# LAUNCHXL-F28379D_3.net
KiCad netlist of a schematic drawn in Altium Designer
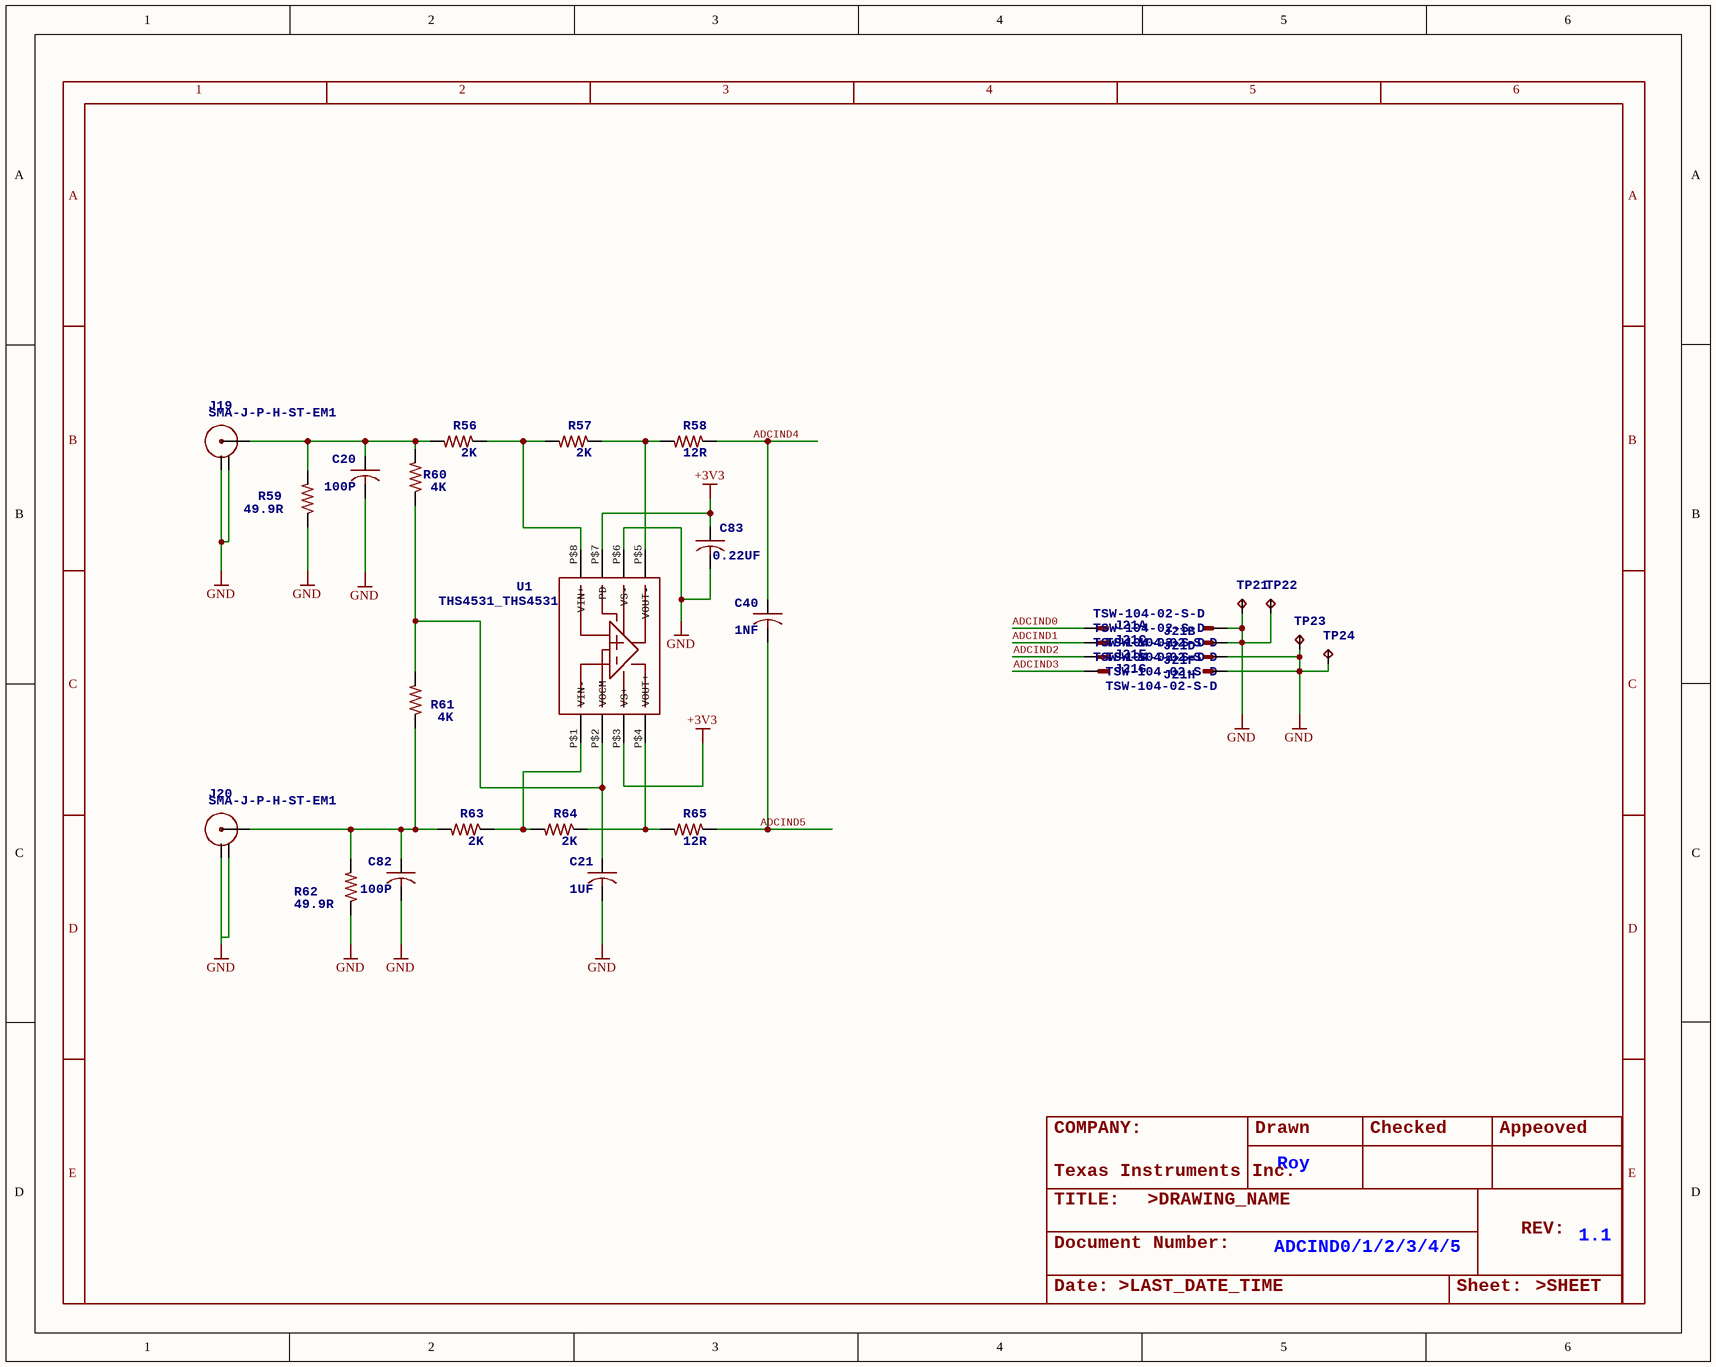
[diagram p0: LAUNCHXL-F28379D_3.SchDoc]

(export (version "E")
  (design (tool "Eeschema 10.0.6"))
  (components
    (comp (ref "C20")
      (value "100P")
      (footprint "C0402")
      (description "<B>CAPACITOR</B>, American symbol")
      (libsource (lib "rcl") (part "C-USC0402"))
    )
    (comp (ref "C21")
      (value "1UF")
      (footprint "C0402")
      (description "<B>CAPACITOR</B>, American symbol")
      (libsource (lib "rcl") (part "C-USC0402"))
    )
    (comp (ref "C40")
      (value "1NF")
      (footprint "C0402")
      (description "<B>CAPACITOR</B>, American symbol")
      (libsource (lib "rcl") (part "C-USC0402"))
    )
    (comp (ref "C82")
      (value "100P")
      (footprint "C0402")
      (description "<B>CAPACITOR</B>, American symbol")
      (libsource (lib "rcl") (part "C-USC0402"))
    )
    (comp (ref "C83")
      (value "0.22UF")
      (footprint "C0402")
      (description "<B>CAPACITOR</B>, American symbol")
      (libsource (lib "rcl") (part "C-USC0402"))
    )
    (comp (ref "J19") (value "SMA-J-P-H-ST-EM1") (footprint "SMA_EM") (libsource (lib "ads704") (part "SMA")))
    (comp (ref "J20") (value "SMA-J-P-H-ST-EM1") (footprint "SMA_EM") (libsource (lib "ads704") (part "SMA")))
    (comp (ref "J21")
      (value "TSW-104-02-S-D")
      (footprint "TSW-104-02-S-D")
      (description "<b>THROUGH-HOLE .025\" SQ POST HEADER</b><p>\nSource: Samtec TSW.pdf")
      (libsource (lib "") (part "TSW-104-02-S-D_1"))
    )
    (comp (ref "R56")
      (value "2K")
      (footprint "R0402")
      (description "<B>RESISTOR</B>, American symbol")
      (libsource (lib "rcl") (part "R-US_R0402"))
    )
    (comp (ref "R57")
      (value "2K")
      (footprint "R0402")
      (description "<B>RESISTOR</B>, American symbol")
      (libsource (lib "rcl") (part "R-US_R0402"))
    )
    (comp (ref "R58")
      (value "12R")
      (footprint "R0402")
      (description "<B>RESISTOR</B>, American symbol")
      (libsource (lib "rcl") (part "R-US_R0402"))
    )
    (comp (ref "R59")
      (value "49.9R")
      (footprint "R0402")
      (description "<B>RESISTOR</B>, American symbol")
      (libsource (lib "rcl") (part "R-US_R0402"))
    )
    (comp (ref "R60")
      (value "4K")
      (footprint "R0402")
      (description "<B>RESISTOR</B>, American symbol")
      (libsource (lib "rcl") (part "R-US_R0402"))
    )
    (comp (ref "R61")
      (value "4K")
      (footprint "R0402")
      (description "<B>RESISTOR</B>, American symbol")
      (libsource (lib "rcl") (part "R-US_R0402"))
    )
    (comp (ref "R62")
      (value "49.9R")
      (footprint "R0402")
      (description "<B>RESISTOR</B>, American symbol")
      (libsource (lib "rcl") (part "R-US_R0402"))
    )
    (comp (ref "R63")
      (value "2K")
      (footprint "R0402")
      (description "<B>RESISTOR</B>, American symbol")
      (libsource (lib "rcl") (part "R-US_R0402"))
    )
    (comp (ref "R64")
      (value "2K")
      (footprint "R0402")
      (description "<B>RESISTOR</B>, American symbol")
      (libsource (lib "rcl") (part "R-US_R0402"))
    )
    (comp (ref "R65")
      (value "12R")
      (footprint "R0402")
      (description "<B>RESISTOR</B>, American symbol")
      (libsource (lib "rcl") (part "R-US_R0402"))
    )
    (comp (ref "TP21")
      (value "TESTPAD_TPB1,27")
      (footprint "TESTPAD_B1,27")
      (description "<b>Test pad</b>")
      (libsource (lib "RF430FRL152H_EVM_a") (part "TESTPAD_TPB1,27"))
    )
    (comp (ref "TP22")
      (value "TESTPAD_TPB1,27")
      (footprint "TESTPAD_B1,27")
      (description "<b>Test pad</b>")
      (libsource (lib "RF430FRL152H_EVM_a") (part "TESTPAD_TPB1,27"))
    )
    (comp (ref "TP23")
      (value "TESTPAD_TPB1,27")
      (footprint "TESTPAD_B1,27")
      (description "<b>Test pad</b>")
      (libsource (lib "RF430FRL152H_EVM_a") (part "TESTPAD_TPB1,27"))
    )
    (comp (ref "TP24")
      (value "TESTPAD_TPB1,27")
      (footprint "TESTPAD_B1,27")
      (description "<b>Test pad</b>")
      (libsource (lib "RF430FRL152H_EVM_a") (part "TESTPAD_TPB1,27"))
    )
    (comp (ref "U1")
      (value "THS4531_THS4531")
      (footprint "THS4531_THS4531")
      (libsource (lib "THS4531") (part "THS4531_THS4531"))
    )
  )
  (nets
    (net (code "1") (name "+3V3") (class "Default")
      (node (ref "C83") (pin "1") (pinfunction "1_1") (pintype "passive"))
      (node (ref "U1") (pin "P$3") (pinfunction "VS+_P$3") (pintype "passive"))
      (node (ref "U1") (pin "P$7") (pinfunction "PD_P$7") (pintype "passive"))
    )
    (net (code "2") (name "/ADCIND0") (class "Default")
      (node (ref "J21") (pin "1") (pinfunction "1_1") (pintype "passive"))
    )
    (net (code "3") (name "/ADCIND1") (class "Default")
      (node (ref "J21") (pin "3") (pinfunction "1_3") (pintype "passive"))
    )
    (net (code "4") (name "/ADCIND2") (class "Default")
      (node (ref "J21") (pin "5") (pinfunction "1_5") (pintype "passive"))
    )
    (net (code "5") (name "/ADCIND3") (class "Default")
      (node (ref "J21") (pin "7") (pinfunction "1_7") (pintype "passive"))
    )
    (net (code "6") (name "/ADCIND4") (class "Default")
      (node (ref "C40") (pin "1") (pinfunction "1_1") (pintype "passive"))
      (node (ref "R58") (pin "1") (pinfunction "1_1") (pintype "passive"))
    )
    (net (code "7") (name "/ADCIND5") (class "Default")
      (node (ref "C40") (pin "2") (pinfunction "2_2") (pintype "passive"))
      (node (ref "R65") (pin "1") (pinfunction "1_1") (pintype "passive"))
    )
    (net (code "8") (name "GND") (class "Default")
      (node (ref "C20") (pin "2") (pinfunction "2_2") (pintype "passive"))
      (node (ref "C21") (pin "2") (pinfunction "2_2") (pintype "passive"))
      (node (ref "C82") (pin "2") (pinfunction "2_2") (pintype "passive"))
      (node (ref "C83") (pin "2") (pinfunction "2_2") (pintype "passive"))
      (node (ref "J19") (pin "1") (pinfunction "1_1") (pintype "passive"))
      (node (ref "J19") (pin "3_4_5") (pinfunction "3_3_4_5") (pintype "passive"))
      (node (ref "J20") (pin "1") (pinfunction "1_1") (pintype "passive"))
      (node (ref "J20") (pin "3_4_5") (pinfunction "3_3_4_5") (pintype "passive"))
      (node (ref "J21") (pin "2") (pinfunction "1_2") (pintype "passive"))
      (node (ref "J21") (pin "4") (pinfunction "1_4") (pintype "passive"))
      (node (ref "J21") (pin "6") (pinfunction "1_6") (pintype "passive"))
      (node (ref "J21") (pin "8") (pinfunction "1_8") (pintype "passive"))
      (node (ref "R59") (pin "1") (pinfunction "1_1") (pintype "passive"))
      (node (ref "R62") (pin "1") (pinfunction "1_1") (pintype "passive"))
      (node (ref "TP21") (pin "TP") (pinfunction "TP_TP") (pintype "passive"))
      (node (ref "TP22") (pin "TP") (pinfunction "TP_TP") (pintype "passive"))
      (node (ref "TP23") (pin "TP") (pinfunction "TP_TP") (pintype "passive"))
      (node (ref "TP24") (pin "TP") (pinfunction "TP_TP") (pintype "passive"))
      (node (ref "U1") (pin "P$6") (pinfunction "VS-_P$6") (pintype "passive"))
    )
    (net (code "9") (name "Net-(C20-Pad1)") (class "Default")
      (node (ref "C20") (pin "1") (pinfunction "1_1") (pintype "passive"))
      (node (ref "J19") (pin "2") (pinfunction "2_2") (pintype "passive"))
      (node (ref "R56") (pin "2") (pinfunction "2_2") (pintype "passive"))
      (node (ref "R59") (pin "2") (pinfunction "2_2") (pintype "passive"))
      (node (ref "R60") (pin "2") (pinfunction "2_2") (pintype "passive"))
    )
    (net (code "10") (name "Net-(C82-Pad1)") (class "Default")
      (node (ref "C82") (pin "1") (pinfunction "1_1") (pintype "passive"))
      (node (ref "J20") (pin "2") (pinfunction "2_2") (pintype "passive"))
      (node (ref "R61") (pin "1") (pinfunction "1_1") (pintype "passive"))
      (node (ref "R62") (pin "2") (pinfunction "2_2") (pintype "passive"))
      (node (ref "R63") (pin "2") (pinfunction "2_2") (pintype "passive"))
    )
    (net (code "11") (name "Net-(U1-VIN+)") (class "Default")
      (node (ref "R56") (pin "1") (pinfunction "1_1") (pintype "passive"))
      (node (ref "R57") (pin "2") (pinfunction "2_2") (pintype "passive"))
      (node (ref "U1") (pin "P$8") (pinfunction "VIN+_P$8") (pintype "passive"))
    )
    (net (code "12") (name "Net-(U1-VIN-)") (class "Default")
      (node (ref "R63") (pin "1") (pinfunction "1_1") (pintype "passive"))
      (node (ref "R64") (pin "2") (pinfunction "2_2") (pintype "passive"))
      (node (ref "U1") (pin "P$1") (pinfunction "VIN-_P$1") (pintype "passive"))
    )
    (net (code "13") (name "Net-(U1-VOCM)") (class "Default")
      (node (ref "C21") (pin "1") (pinfunction "1_1") (pintype "passive"))
      (node (ref "R60") (pin "1") (pinfunction "1_1") (pintype "passive"))
      (node (ref "R61") (pin "2") (pinfunction "2_2") (pintype "passive"))
      (node (ref "U1") (pin "P$2") (pinfunction "VOCM_P$2") (pintype "passive"))
    )
    (net (code "14") (name "Net-(U1-VOUT+)") (class "Default")
      (node (ref "R64") (pin "1") (pinfunction "1_1") (pintype "passive"))
      (node (ref "R65") (pin "2") (pinfunction "2_2") (pintype "passive"))
      (node (ref "U1") (pin "P$4") (pinfunction "VOUT+_P$4") (pintype "passive"))
    )
    (net (code "15") (name "Net-(U1-VOUT-)") (class "Default")
      (node (ref "R57") (pin "1") (pinfunction "1_1") (pintype "passive"))
      (node (ref "R58") (pin "2") (pinfunction "2_2") (pintype "passive"))
      (node (ref "U1") (pin "P$5") (pinfunction "VOUT-_P$5") (pintype "passive"))
    )
  )
)
